# POWER_POSITIVE.net
KiCad netlist of a schematic drawn in Altium Designer
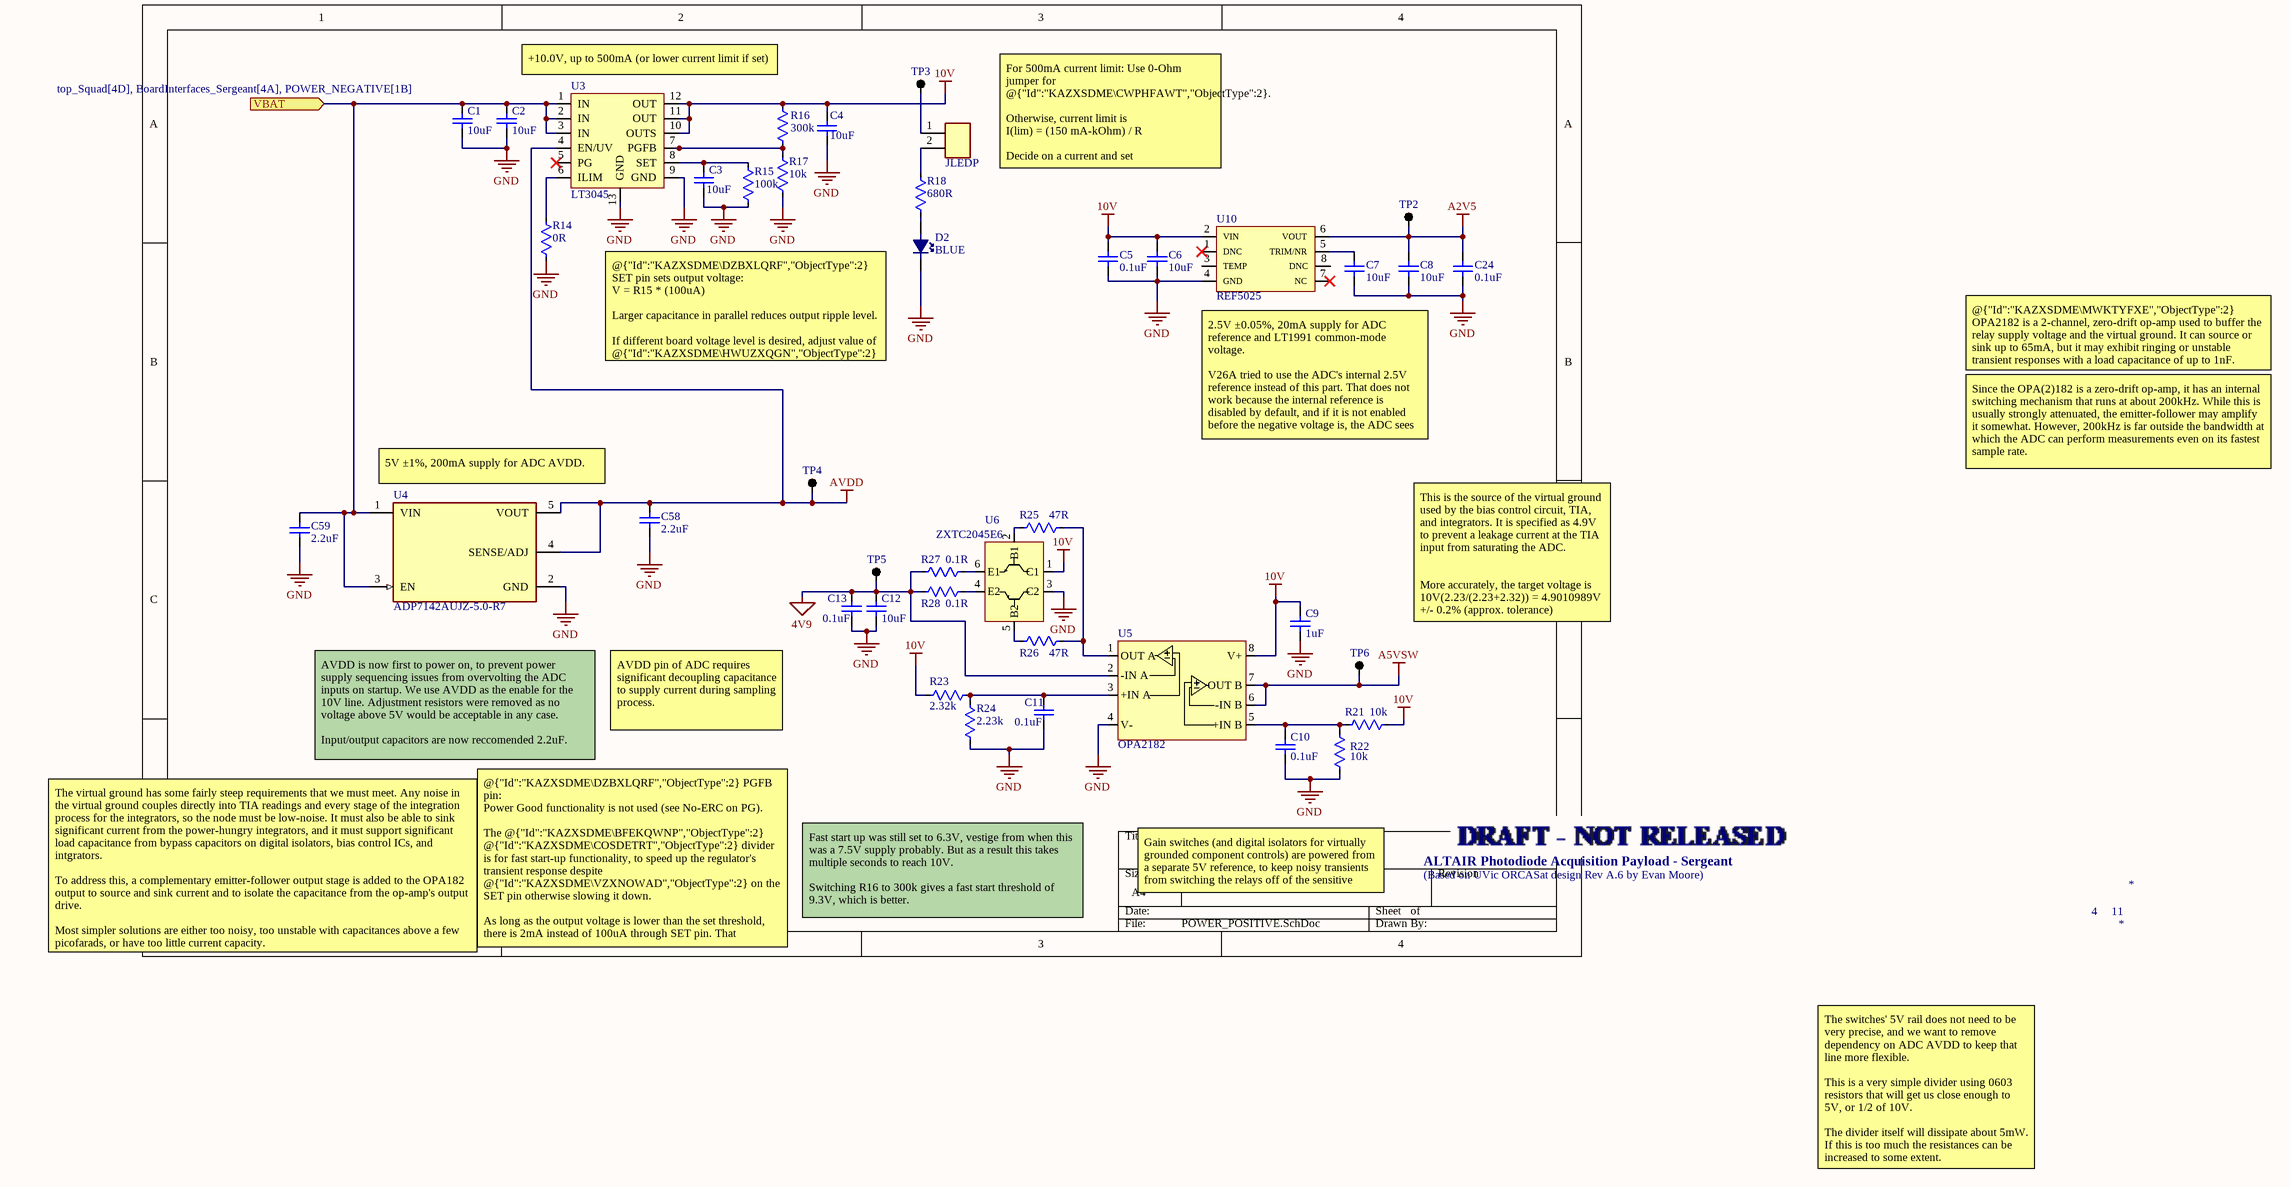
[diagram p0: POWER_POSITIVE.SchDoc]

(export (version "E")
  (design (tool "Eeschema 10.0.6"))
  (components
    (comp (ref "C1")
      (value "10uF")
      (footprint "CAP 1206 IPC LOW DENSITY")
      (description "Murata GRT319R6YA106KE01D - Cap Ceramic 10uF 35V X5R 10% Pad SMD 1206 85C Automotive T/R")
      (fields (field (name "MF") "Murata") (field (name "MP") "GRT319R6YA106KE01D"))
      (libsource (lib "ALTAIR_PD_Capacitors") (part "CAP"))
    )
    (comp (ref "C2")
      (value "10uF")
      (footprint "CAP 1206 IPC LOW DENSITY")
      (description "Murata GRT319R6YA106KE01D - Cap Ceramic 10uF 35V X5R 10% Pad SMD 1206 85C Automotive T/R")
      (fields (field (name "MF") "Murata") (field (name "MP") "GRT319R6YA106KE01D"))
      (libsource (lib "ALTAIR_PD_Capacitors") (part "CAP"))
    )
    (comp (ref "C3")
      (value "10uF")
      (footprint "CAP 1206 IPC LOW DENSITY")
      (description "Murata GRT319R6YA106KE01D - Cap Ceramic 10uF 35V X5R 10% Pad SMD 1206 85C Automotive T/R")
      (fields (field (name "MF") "Murata") (field (name "MP") "GRT319R6YA106KE01D"))
      (libsource (lib "ALTAIR_PD_Capacitors") (part "CAP"))
    )
    (comp (ref "C4")
      (value "10uF")
      (footprint "CAP 1206 IPC LOW DENSITY")
      (description "Murata GRT319R6YA106KE01D - Cap Ceramic 10uF 35V X5R 10% Pad SMD 1206 85C Automotive T/R")
      (fields (field (name "MF") "Murata") (field (name "MP") "GRT319R6YA106KE01D"))
      (libsource (lib "ALTAIR_PD_Capacitors") (part "CAP"))
    )
    (comp (ref "C5")
      (value "0.1uF")
      (footprint "CAP 0603 IPC MID DENSITY")
      (description "Kemet C0603C104K5RACAUTO - Cap Ceramic 0.1uF 50V X7R 10% 0603 125C Paper T/R")
      (fields (field (name "MF") "Kemet") (field (name "MP") "C0603C104K5RACAUTO"))
      (libsource (lib "ALTAIR_PD_Capacitors") (part "CAP"))
    )
    (comp (ref "C6")
      (value "10uF")
      (footprint "CAP 0805 IPC MID DENSITY")
      (description "Murata GRM21BR61E106KA73L - Cap Ceramic 10uF 10% 25V X5R 0805")
      (fields (field (name "MF") "Murata") (field (name "MP") "GRM21BR61E106KA73L"))
      (libsource (lib "ALTAIR_PD_Capacitors") (part "CAP"))
    )
    (comp (ref "C7")
      (value "10uF")
      (footprint "CAP 0805 IPC MID DENSITY")
      (description "Murata GRM21BR61E106KA73L - Cap Ceramic 10uF 10% 25V X5R 0805")
      (fields (field (name "MF") "Murata") (field (name "MP") "GRM21BR61E106KA73L"))
      (libsource (lib "ALTAIR_PD_Capacitors") (part "CAP"))
    )
    (comp (ref "C8")
      (value "10uF")
      (footprint "CAP 0805 IPC MID DENSITY")
      (description "Murata GRM21BR61E106KA73L - Cap Ceramic 10uF 10% 25V X5R 0805")
      (fields (field (name "MF") "Murata") (field (name "MP") "GRM21BR61E106KA73L"))
      (libsource (lib "ALTAIR_PD_Capacitors") (part "CAP"))
    )
    (comp (ref "C9")
      (value "1uF")
      (footprint "CAP 0603 IPC MID DENSITY")
      (description "Murata GRT188R61H105KE13D - Cap MLCC AEC-Q200 X5R 1uF 50V 0603")
      (fields (field (name "MF") "Murata") (field (name "MP") "GRT188R61H105KE13D"))
      (libsource (lib "ALTAIR_PD_Capacitors") (part "CAP"))
    )
    (comp (ref "C10")
      (value "0.1uF")
      (footprint "CAP 0603 IPC MID DENSITY")
      (description "Kemet C0603C104K5RACAUTO - Cap Ceramic 0.1uF 50V X7R 10% 0603 125C Paper T/R")
      (fields (field (name "MF") "Kemet") (field (name "MP") "C0603C104K5RACAUTO"))
      (libsource (lib "ALTAIR_PD_Capacitors") (part "CAP"))
    )
    (comp (ref "C11")
      (value "0.1uF")
      (footprint "CAP 0603 IPC MID DENSITY")
      (description "Kemet C0603C104K5RACAUTO - Cap Ceramic 0.1uF 50V X7R 10% 0603 125C Paper T/R")
      (fields (field (name "MF") "Kemet") (field (name "MP") "C0603C104K5RACAUTO"))
      (libsource (lib "ALTAIR_PD_Capacitors") (part "CAP"))
    )
    (comp (ref "C12")
      (value "10uF")
      (footprint "CAP 1206 IPC LOW DENSITY")
      (description "Murata GRT319R6YA106KE01D - Cap Ceramic 10uF 35V X5R 10% Pad SMD 1206 85C Automotive T/R")
      (fields (field (name "MF") "Murata") (field (name "MP") "GRT319R6YA106KE01D"))
      (libsource (lib "ALTAIR_PD_Capacitors") (part "CAP"))
    )
    (comp (ref "C13")
      (value "0.1uF")
      (footprint "CAP 0603 IPC MID DENSITY")
      (description "Kemet C0603C104K5RACAUTO - Cap Ceramic 0.1uF 50V X7R 10% 0603 125C Paper T/R")
      (fields (field (name "MF") "Kemet") (field (name "MP") "C0603C104K5RACAUTO"))
      (libsource (lib "ALTAIR_PD_Capacitors") (part "CAP"))
    )
    (comp (ref "C24")
      (value "0.1uF")
      (footprint "CAP 0603 IPC MID DENSITY")
      (description "Kemet C0603C104K5RACAUTO - Cap Ceramic 0.1uF 50V X7R 10% 0603 125C Paper T/R")
      (fields (field (name "MF") "Kemet") (field (name "MP") "C0603C104K5RACAUTO"))
      (libsource (lib "ALTAIR_PD_Capacitors") (part "CAP"))
    )
    (comp (ref "C58")
      (value "2.2uF")
      (footprint "CAP 1206 UNKNOWN")
      (description "CL31B225KBHNNNE CAP CER 2.2UF 50V X7R 1206")
      (fields (field (name "MF") "Samsung Electro-Mechanics") (field (name "MP") "CL31B225KBHNNNE"))
      (libsource (lib "ALTAIR_PD_Capacitors") (part "CAP"))
    )
    (comp (ref "C59")
      (value "2.2uF")
      (footprint "CAP 1206 UNKNOWN")
      (description "CL31B225KBHNNNE CAP CER 2.2UF 50V X7R 1206")
      (fields (field (name "MF") "Samsung Electro-Mechanics") (field (name "MP") "CL31B225KBHNNNE"))
      (libsource (lib "ALTAIR_PD_Capacitors") (part "CAP"))
    )
    (comp (ref "D2")
      (value "BLUE")
      (footprint "LED 0603 MID DENSITY")
      (description "LED BLUE CLEAR 0603 SMD")
      (fields (field (name "MF") "Wurth Electronics") (field (name "MP") "150060BS75000"))
      (libsource (lib "ALTAIR_PD_Diodes") (part "LED-blue"))
    )
    (comp (ref "JLEDP")
      (value "JLED")
      (footprint "ALTAIR_PD_Headers:JUMPER 2POS 1MM PITCH THT")
      (description "2x1 Header THT 1mm Pitch")
      (fields
        (field (name "MF") "GCT (GLOBAL CONNECTOR TECHNOLOGY)")
        (field (name "MP") "BC020-02-A-0200-0300-L-G")
      )
      (libsource (lib "ALTAIR_PD_Headers") (part "BC020-02-A-0200-0300-L-G"))
    )
    (comp (ref "R14")
      (value "0R")
      (footprint "RES 0603 IPC MID DENSITY")
      (description "Vishay CRCW06030000Z0EA - Res 0 Ohms 1/8W SMD 0603")
      (fields (field (name "MF") "Vishay Dale") (field (name "MP") "CRCW06030000Z0EA"))
      (libsource (lib "ALTAIR_PD_Resistors") (part "RES"))
    )
    (comp (ref "R15")
      (value "100k")
      (footprint "RES 0603 IPC MID DENSITY")
      (description "Panasonic ERA-3ARB104V - Res SMD 0603 0.1% 0.10W T.C. 10ppm 100K")
      (fields (field (name "MF") "Panasonic Electronic Components") (field (name "MP") "ERA-3ARB104V"))
      (libsource (lib "ALTAIR_PD_Resistors") (part "RES"))
    )
    (comp (ref "R16")
      (value "300k")
      (footprint "RES 0603 IPC MID DENSITY")
      (description "Vishay MCT06030C3003FP500 - Res SMD 300kOhm 1% 1/10W 0603")
      (fields (field (name "MF") "Vishay Dale") (field (name "MP") "MCT06030C3003FP500"))
      (libsource (lib "ALTAIR_PD_Resistors") (part "RES"))
    )
    (comp (ref "R17")
      (value "10k")
      (footprint "RES 0603 IPC MID DENSITY")
      (description "Vishay CRCW060310K0FKEA SMD 0603 10k, CRCW e3 Series, 75V, thick film, 100mW")
      (fields (field (name "MF") "Vishay Dale") (field (name "MP") "CRCW060310K0FKEA"))
      (libsource (lib "ALTAIR_PD_Resistors") (part "RES"))
    )
    (comp (ref "R18")
      (value "680R")
      (footprint "RES 0603 IPC MID DENSITY")
      (description "Panasonic ERJ-3EKF6800V - Res SMD 680 Ohm 1% 1/10W 0603")
      (fields (field (name "MF") "Panasonic Electronic Components") (field (name "MP") "ERJ-3EKF6800V"))
      (libsource (lib "ALTAIR_PD_Resistors") (part "RES"))
    )
    (comp (ref "R21")
      (value "10k")
      (footprint "RES 0603 IPC MID DENSITY")
      (description "Vishay CRCW060310K0FKEA SMD 0603 10k, CRCW e3 Series, 75V, thick film, 100mW")
      (fields (field (name "MF") "Vishay Dale") (field (name "MP") "CRCW060310K0FKEA"))
      (libsource (lib "ALTAIR_PD_Resistors") (part "RES"))
    )
    (comp (ref "R22")
      (value "10k")
      (footprint "RES 0603 IPC MID DENSITY")
      (description "Vishay CRCW060310K0FKEA SMD 0603 10k, CRCW e3 Series, 75V, thick film, 100mW")
      (fields (field (name "MF") "Vishay Dale") (field (name "MP") "CRCW060310K0FKEA"))
      (libsource (lib "ALTAIR_PD_Resistors") (part "RES"))
    )
    (comp (ref "R23")
      (value "2.32k")
      (footprint "RES 0603 IPC MID DENSITY")
      (description "Vishay TNPW06032K32BEEA - Res 2.32k 0.1% 0.21W SMD 0603")
      (fields (field (name "MF") "Vishay Dale") (field (name "MP") "TNPW06032K32BEEA"))
      (libsource (lib "ALTAIR_PD_Resistors") (part "RES"))
    )
    (comp (ref "R24")
      (value "2.23k")
      (footprint "RES 0603 IPC MID DENSITY")
      (description "KOA Speer RN73R1JTTD2231B25 - Res 2.23k 0.1% 1/10W SMD 0603")
      (fields (field (name "MF") "KOA Speer Electronics, Inc.") (field (name "MP") "RN73R1JTTD2231B25"))
      (libsource (lib "ALTAIR_PD_Resistors") (part "RES"))
    )
    (comp (ref "R25")
      (value "47R")
      (footprint "RES 0402 NON-IPC SEI")
      (description "Stackpole RMCF0402JT47R0 - Res 47Ohm 5% 0.063W 0402 Thick Film AEC-Q200 compliant")
      (fields (field (name "MF") "Stackpole Electronics Inc.") (field (name "MP") "RMCF0402JT47R0"))
      (libsource (lib "ALTAIR_PD_Resistors") (part "RES"))
    )
    (comp (ref "R26")
      (value "47R")
      (footprint "RES 0402 NON-IPC SEI")
      (description "Stackpole RMCF0402JT47R0 - Res 47Ohm 5% 0.063W 0402 Thick Film AEC-Q200 compliant")
      (fields (field (name "MF") "Stackpole Electronics Inc.") (field (name "MP") "RMCF0402JT47R0"))
      (libsource (lib "ALTAIR_PD_Resistors") (part "RES"))
    )
    (comp (ref "R27")
      (value "0.1R")
      (footprint "RES 0402 NON-IPC YAGEO")
      (description "Yageo RL0402JR-070R1L - Res 0.1Ohm 5% 1/16W SMD 0402")
      (fields (field (name "MF") "YAGEO") (field (name "MP") "RL0402JR-070R1L"))
      (libsource (lib "ALTAIR_PD_Resistors") (part "RES"))
    )
    (comp (ref "R28")
      (value "0.1R")
      (footprint "RES 0402 NON-IPC YAGEO")
      (description "Yageo RL0402JR-070R1L - Res 0.1Ohm 5% 1/16W SMD 0402")
      (fields (field (name "MF") "YAGEO") (field (name "MP") "RL0402JR-070R1L"))
      (libsource (lib "ALTAIR_PD_Resistors") (part "RES"))
    )
    (comp (ref "TP2")
      (value "Testpoint")
      (footprint "TESTPOINT THT")
      (libsource (lib "ALTAIR_PD_Testpoint") (part "Testpoint"))
    )
    (comp (ref "TP3")
      (value "Testpoint")
      (footprint "TESTPOINT THT")
      (libsource (lib "ALTAIR_PD_Testpoint") (part "Testpoint"))
    )
    (comp (ref "TP4")
      (value "Testpoint")
      (footprint "TESTPOINT THT")
      (libsource (lib "ALTAIR_PD_Testpoint") (part "Testpoint"))
    )
    (comp (ref "TP5")
      (value "Testpoint")
      (footprint "TESTPOINT THT")
      (libsource (lib "ALTAIR_PD_Testpoint") (part "Testpoint"))
    )
    (comp (ref "TP6")
      (value "Testpoint")
      (footprint "TESTPOINT THT")
      (libsource (lib "ALTAIR_PD_Testpoint") (part "Testpoint"))
    )
    (comp (ref "U3")
      (value "LT3045")
      (footprint "12-TSOP 0.65MM PITCH 3MM WIDTH EP IPC MID DENSITY")
      (description "20V 500mA Ultralow Noise Ultrahigh PSRR Adjustable Linear Regulator 260V Dropout MSOP-12")
      (fields (field (name "MF") "Analog Devices / Linear Technology") (field (name "MP") "LT3045EMSE#PBF"))
      (libsource (lib "ALTAIR_PD_Regulators") (part "LT3045"))
    )
    (comp (ref "U4")
      (value "ADP7142AUJZ-5.0-R7")
      (footprint "SOT23-5 HIGH DENSITY AD")
      (description "1.2-40V 200mA Low Noise CMOS LDO Adjustable Linear Regulator TSOT23")
      (fields
        (field (name "OCTOPART") "https://octopart.com/adp7142aujz-r7-analog+devices-38928114")
        (field (name "MF") "Analog Devices")
      )
      (libsource (lib "ALTAIR_PD_Regulators") (part "ADP7142AUJZ-R7"))
    )
    (comp (ref "U5")
      (value "OPA2182")
      (footprint "8-TSSOP 0.65MM PITCH 4.4MM WIDTH IPC MID DENSITY")
      (fields (field (name "MF") "Texas Instruments") (field (name "MP") "OPA2182IDGKR"))
      (libsource (lib "ALTAIR_PD_Amplifiers") (part "OPA2182IDBV"))
    )
    (comp (ref "U6")
      (value "ZXTC2045E6")
      (footprint "SOT23-6 NON-IPC DIODES")
      (description "BJT Array, 1NPN 1PNP, VCE(sat) 375mV, hFE 300, Breakdown 30V, 6-SOT-23")
      (fields (field (name "MF") "Diodes Incorporated") (field (name "MP") "ZXTC2045E6TA"))
      (libsource (lib "ALTAIR_PD_BJTs") (part "ZXTC2045E6"))
    )
    (comp (ref "U10")
      (value "REF5025")
      (footprint "8-TSOP 0.65MM PITCH 3MM WIDTH IPC MID DENSITY")
      (description "2.5V±0.05% Voltage Reference 8VSSOP")
      (fields (field (name "MF") "Texas Instruments") (field (name "MP") "REF5025IDGKR"))
      (libsource (lib "ALTAIR_PD_MiscPower") (part "REF5050IDGKR"))
    )
  )
  (nets
    (net (code "1") (name "/VBAT") (class "Default")
      (node (ref "C1") (pin "2") (pinfunction "2_2") (pintype "passive"))
      (node (ref "C2") (pin "2") (pinfunction "2_2") (pintype "passive"))
      (node (ref "C59") (pin "1") (pinfunction "1_1") (pintype "passive"))
      (node (ref "U3") (pin "1") (pinfunction "IN_1") (pintype "passive"))
      (node (ref "U3") (pin "2") (pinfunction "IN_2") (pintype "passive"))
      (node (ref "U3") (pin "3") (pinfunction "IN_3") (pintype "passive"))
      (node (ref "U4") (pin "1") (pinfunction "VIN_1") (pintype "power_in"))
      (node (ref "U4") (pin "3") (pinfunction "EN_3") (pintype "input"))
    )
    (net (code "2") (name "4V9") (class "Default")
      (node (ref "C12") (pin "2") (pinfunction "2_2") (pintype "passive"))
      (node (ref "C13") (pin "2") (pinfunction "2_2") (pintype "passive"))
      (node (ref "R27") (pin "1") (pinfunction "1_1") (pintype "passive"))
      (node (ref "R28") (pin "1") (pinfunction "1_1") (pintype "passive"))
      (node (ref "TP5") (pin "1") (pinfunction "1_1") (pintype "passive"))
      (node (ref "U5") (pin "2") (pinfunction "-IN_A_2") (pintype "passive"))
    )
    (net (code "3") (name "10V") (class "Default")
      (node (ref "C4") (pin "2") (pinfunction "2_2") (pintype "passive"))
      (node (ref "C5") (pin "1") (pinfunction "1_1") (pintype "passive"))
      (node (ref "C6") (pin "2") (pinfunction "2_2") (pintype "passive"))
      (node (ref "C9") (pin "2") (pinfunction "2_2") (pintype "passive"))
      (node (ref "JLEDP") (pin "1") (pinfunction "1_1") (pintype "passive"))
      (node (ref "R16") (pin "2") (pinfunction "2_2") (pintype "passive"))
      (node (ref "R21") (pin "2") (pinfunction "2_2") (pintype "passive"))
      (node (ref "R23") (pin "2") (pinfunction "2_2") (pintype "passive"))
      (node (ref "TP3") (pin "1") (pinfunction "1_1") (pintype "passive"))
      (node (ref "U10") (pin "2") (pinfunction "VIN_2") (pintype "passive"))
      (node (ref "U3") (pin "10") (pinfunction "OUTS_10") (pintype "passive"))
      (node (ref "U3") (pin "11") (pinfunction "OUT_11") (pintype "passive"))
      (node (ref "U3") (pin "12") (pinfunction "OUT_12") (pintype "passive"))
      (node (ref "U5") (pin "8") (pinfunction "V+_8") (pintype "passive"))
      (node (ref "U6") (pin "1") (pinfunction "C1_1") (pintype "passive"))
    )
    (net (code "4") (name "A2V5") (class "Default")
      (node (ref "C24") (pin "1") (pinfunction "1_1") (pintype "passive"))
      (node (ref "C8") (pin "2") (pinfunction "2_2") (pintype "passive"))
      (node (ref "TP2") (pin "1") (pinfunction "1_1") (pintype "passive"))
      (node (ref "U10") (pin "6") (pinfunction "VOUT_6") (pintype "passive"))
    )
    (net (code "5") (name "A5VSW") (class "Default")
      (node (ref "TP6") (pin "1") (pinfunction "1_1") (pintype "passive"))
      (node (ref "U5") (pin "6") (pinfunction "-IN_B_6") (pintype "passive"))
      (node (ref "U5") (pin "7") (pinfunction "OUT_B_7") (pintype "passive"))
    )
    (net (code "6") (name "AVDD") (class "Default")
      (node (ref "C58") (pin "1") (pinfunction "1_1") (pintype "passive"))
      (node (ref "TP4") (pin "1") (pinfunction "1_1") (pintype "passive"))
      (node (ref "U3") (pin "4") (pinfunction "EN/UV_4") (pintype "passive"))
      (node (ref "U4") (pin "4") (pinfunction "SENSE/ADJ_4") (pintype "passive"))
      (node (ref "U4") (pin "5") (pinfunction "VOUT_5") (pintype "passive"))
    )
    (net (code "7") (name "GND") (class "Default")
      (node (ref "C1") (pin "1") (pinfunction "1_1") (pintype "passive"))
      (node (ref "C10") (pin "1") (pinfunction "1_1") (pintype "passive"))
      (node (ref "C11") (pin "1") (pinfunction "1_1") (pintype "passive"))
      (node (ref "C12") (pin "1") (pinfunction "1_1") (pintype "passive"))
      (node (ref "C13") (pin "1") (pinfunction "1_1") (pintype "passive"))
      (node (ref "C2") (pin "1") (pinfunction "1_1") (pintype "passive"))
      (node (ref "C24") (pin "2") (pinfunction "2_2") (pintype "passive"))
      (node (ref "C3") (pin "1") (pinfunction "1_1") (pintype "passive"))
      (node (ref "C4") (pin "1") (pinfunction "1_1") (pintype "passive"))
      (node (ref "C5") (pin "2") (pinfunction "2_2") (pintype "passive"))
      (node (ref "C58") (pin "2") (pinfunction "2_2") (pintype "passive"))
      (node (ref "C59") (pin "2") (pinfunction "2_2") (pintype "passive"))
      (node (ref "C6") (pin "1") (pinfunction "1_1") (pintype "passive"))
      (node (ref "C7") (pin "2") (pinfunction "2_2") (pintype "passive"))
      (node (ref "C8") (pin "1") (pinfunction "1_1") (pintype "passive"))
      (node (ref "C9") (pin "1") (pinfunction "1_1") (pintype "passive"))
      (node (ref "D2") (pin "1") (pinfunction "1_1") (pintype "passive"))
      (node (ref "R14") (pin "1") (pinfunction "1_1") (pintype "passive"))
      (node (ref "R15") (pin "1") (pinfunction "1_1") (pintype "passive"))
      (node (ref "R17") (pin "1") (pinfunction "1_1") (pintype "passive"))
      (node (ref "R22") (pin "1") (pinfunction "1_1") (pintype "passive"))
      (node (ref "R24") (pin "1") (pinfunction "1_1") (pintype "passive"))
      (node (ref "U10") (pin "4") (pinfunction "GND_4") (pintype "passive"))
      (node (ref "U3") (pin "13") (pinfunction "GND_13") (pintype "passive"))
      (node (ref "U3") (pin "9") (pinfunction "GND_9") (pintype "passive"))
      (node (ref "U4") (pin "2") (pinfunction "GND_2") (pintype "power_in"))
      (node (ref "U5") (pin "4") (pinfunction "V-_4") (pintype "passive"))
      (node (ref "U6") (pin "3") (pinfunction "C2_3") (pintype "passive"))
    )
    (net (code "8") (name "Net-(D2-Pad2)") (class "Default")
      (node (ref "D2") (pin "2") (pinfunction "2_2") (pintype "passive"))
      (node (ref "R18") (pin "1") (pinfunction "1_1") (pintype "passive"))
    )
    (net (code "9") (name "Net-(JLEDP-Pad2)") (class "Default")
      (node (ref "JLEDP") (pin "2") (pinfunction "2_2") (pintype "passive"))
      (node (ref "R18") (pin "2") (pinfunction "2_2") (pintype "passive"))
    )
    (net (code "10") (name "Net-(U3-ILIM)") (class "Default")
      (node (ref "R14") (pin "2") (pinfunction "2_2") (pintype "passive"))
      (node (ref "U3") (pin "6") (pinfunction "ILIM_6") (pintype "passive"))
    )
    (net (code "11") (name "Net-(U3-PGFB)") (class "Default")
      (node (ref "R16") (pin "1") (pinfunction "1_1") (pintype "passive"))
      (node (ref "R17") (pin "2") (pinfunction "2_2") (pintype "passive"))
      (node (ref "U3") (pin "7") (pinfunction "PGFB_7") (pintype "passive"))
    )
    (net (code "12") (name "Net-(U3-SET)") (class "Default")
      (node (ref "C3") (pin "2") (pinfunction "2_2") (pintype "passive"))
      (node (ref "R15") (pin "2") (pinfunction "2_2") (pintype "passive"))
      (node (ref "U3") (pin "8") (pinfunction "SET_8") (pintype "passive"))
    )
    (net (code "13") (name "Net-(U5-+IN_A)") (class "Default")
      (node (ref "C11") (pin "2") (pinfunction "2_2") (pintype "passive"))
      (node (ref "R23") (pin "1") (pinfunction "1_1") (pintype "passive"))
      (node (ref "R24") (pin "2") (pinfunction "2_2") (pintype "passive"))
      (node (ref "U5") (pin "3") (pinfunction "+IN_A_3") (pintype "passive"))
    )
    (net (code "14") (name "Net-(U5-+IN_B)") (class "Default")
      (node (ref "C10") (pin "2") (pinfunction "2_2") (pintype "passive"))
      (node (ref "R21") (pin "1") (pinfunction "1_1") (pintype "passive"))
      (node (ref "R22") (pin "2") (pinfunction "2_2") (pintype "passive"))
      (node (ref "U5") (pin "5") (pinfunction "+IN_B_5") (pintype "passive"))
    )
    (net (code "15") (name "Net-(U5-OUT_A)") (class "Default")
      (node (ref "R25") (pin "2") (pinfunction "2_2") (pintype "passive"))
      (node (ref "R26") (pin "2") (pinfunction "2_2") (pintype "passive"))
      (node (ref "U5") (pin "1") (pinfunction "OUT_A_1") (pintype "passive"))
    )
    (net (code "16") (name "Net-(U6-B1)") (class "Default")
      (node (ref "R25") (pin "1") (pinfunction "1_1") (pintype "passive"))
      (node (ref "U6") (pin "2") (pinfunction "B1_2") (pintype "passive"))
    )
    (net (code "17") (name "Net-(U6-B2)") (class "Default")
      (node (ref "R26") (pin "1") (pinfunction "1_1") (pintype "passive"))
      (node (ref "U6") (pin "5") (pinfunction "B2_5") (pintype "passive"))
    )
    (net (code "18") (name "Net-(U6-E1)") (class "Default")
      (node (ref "R27") (pin "2") (pinfunction "2_2") (pintype "passive"))
      (node (ref "U6") (pin "6") (pinfunction "E1_6") (pintype "passive"))
    )
    (net (code "19") (name "Net-(U6-E2)") (class "Default")
      (node (ref "R28") (pin "2") (pinfunction "2_2") (pintype "passive"))
      (node (ref "U6") (pin "4") (pinfunction "E2_4") (pintype "passive"))
    )
    (net (code "20") (name "Net-(U10-TRIM{slash}NR)") (class "Default")
      (node (ref "C7") (pin "1") (pinfunction "1_1") (pintype "passive"))
      (node (ref "U10") (pin "5") (pinfunction "TRIM/NR_5") (pintype "passive"))
    )
    (net (code "21") (name "unconnected-(U3-PG-Pad5)") (class "Default")
      (node (ref "U3") (pin "5") (pinfunction "PG_5") (pintype "passive+no_connect"))
    )
    (net (code "22") (name "unconnected-(U10-DNC-Pad1)") (class "Default")
      (node (ref "U10") (pin "1") (pinfunction "DNC_1") (pintype "passive+no_connect"))
    )
    (net (code "23") (name "unconnected-(U10-DNC-Pad8)") (class "Default")
      (node (ref "U10") (pin "8") (pinfunction "DNC_8") (pintype "passive"))
    )
    (net (code "24") (name "unconnected-(U10-NC-Pad7)") (class "Default")
      (node (ref "U10") (pin "7") (pinfunction "NC_7") (pintype "passive+no_connect"))
    )
    (net (code "25") (name "unconnected-(U10-TEMP-Pad3)") (class "Default")
      (node (ref "U10") (pin "3") (pinfunction "TEMP_3") (pintype "passive"))
    )
  )
)
